# IO.net
KiCad netlist of a schematic drawn in Altium Designer
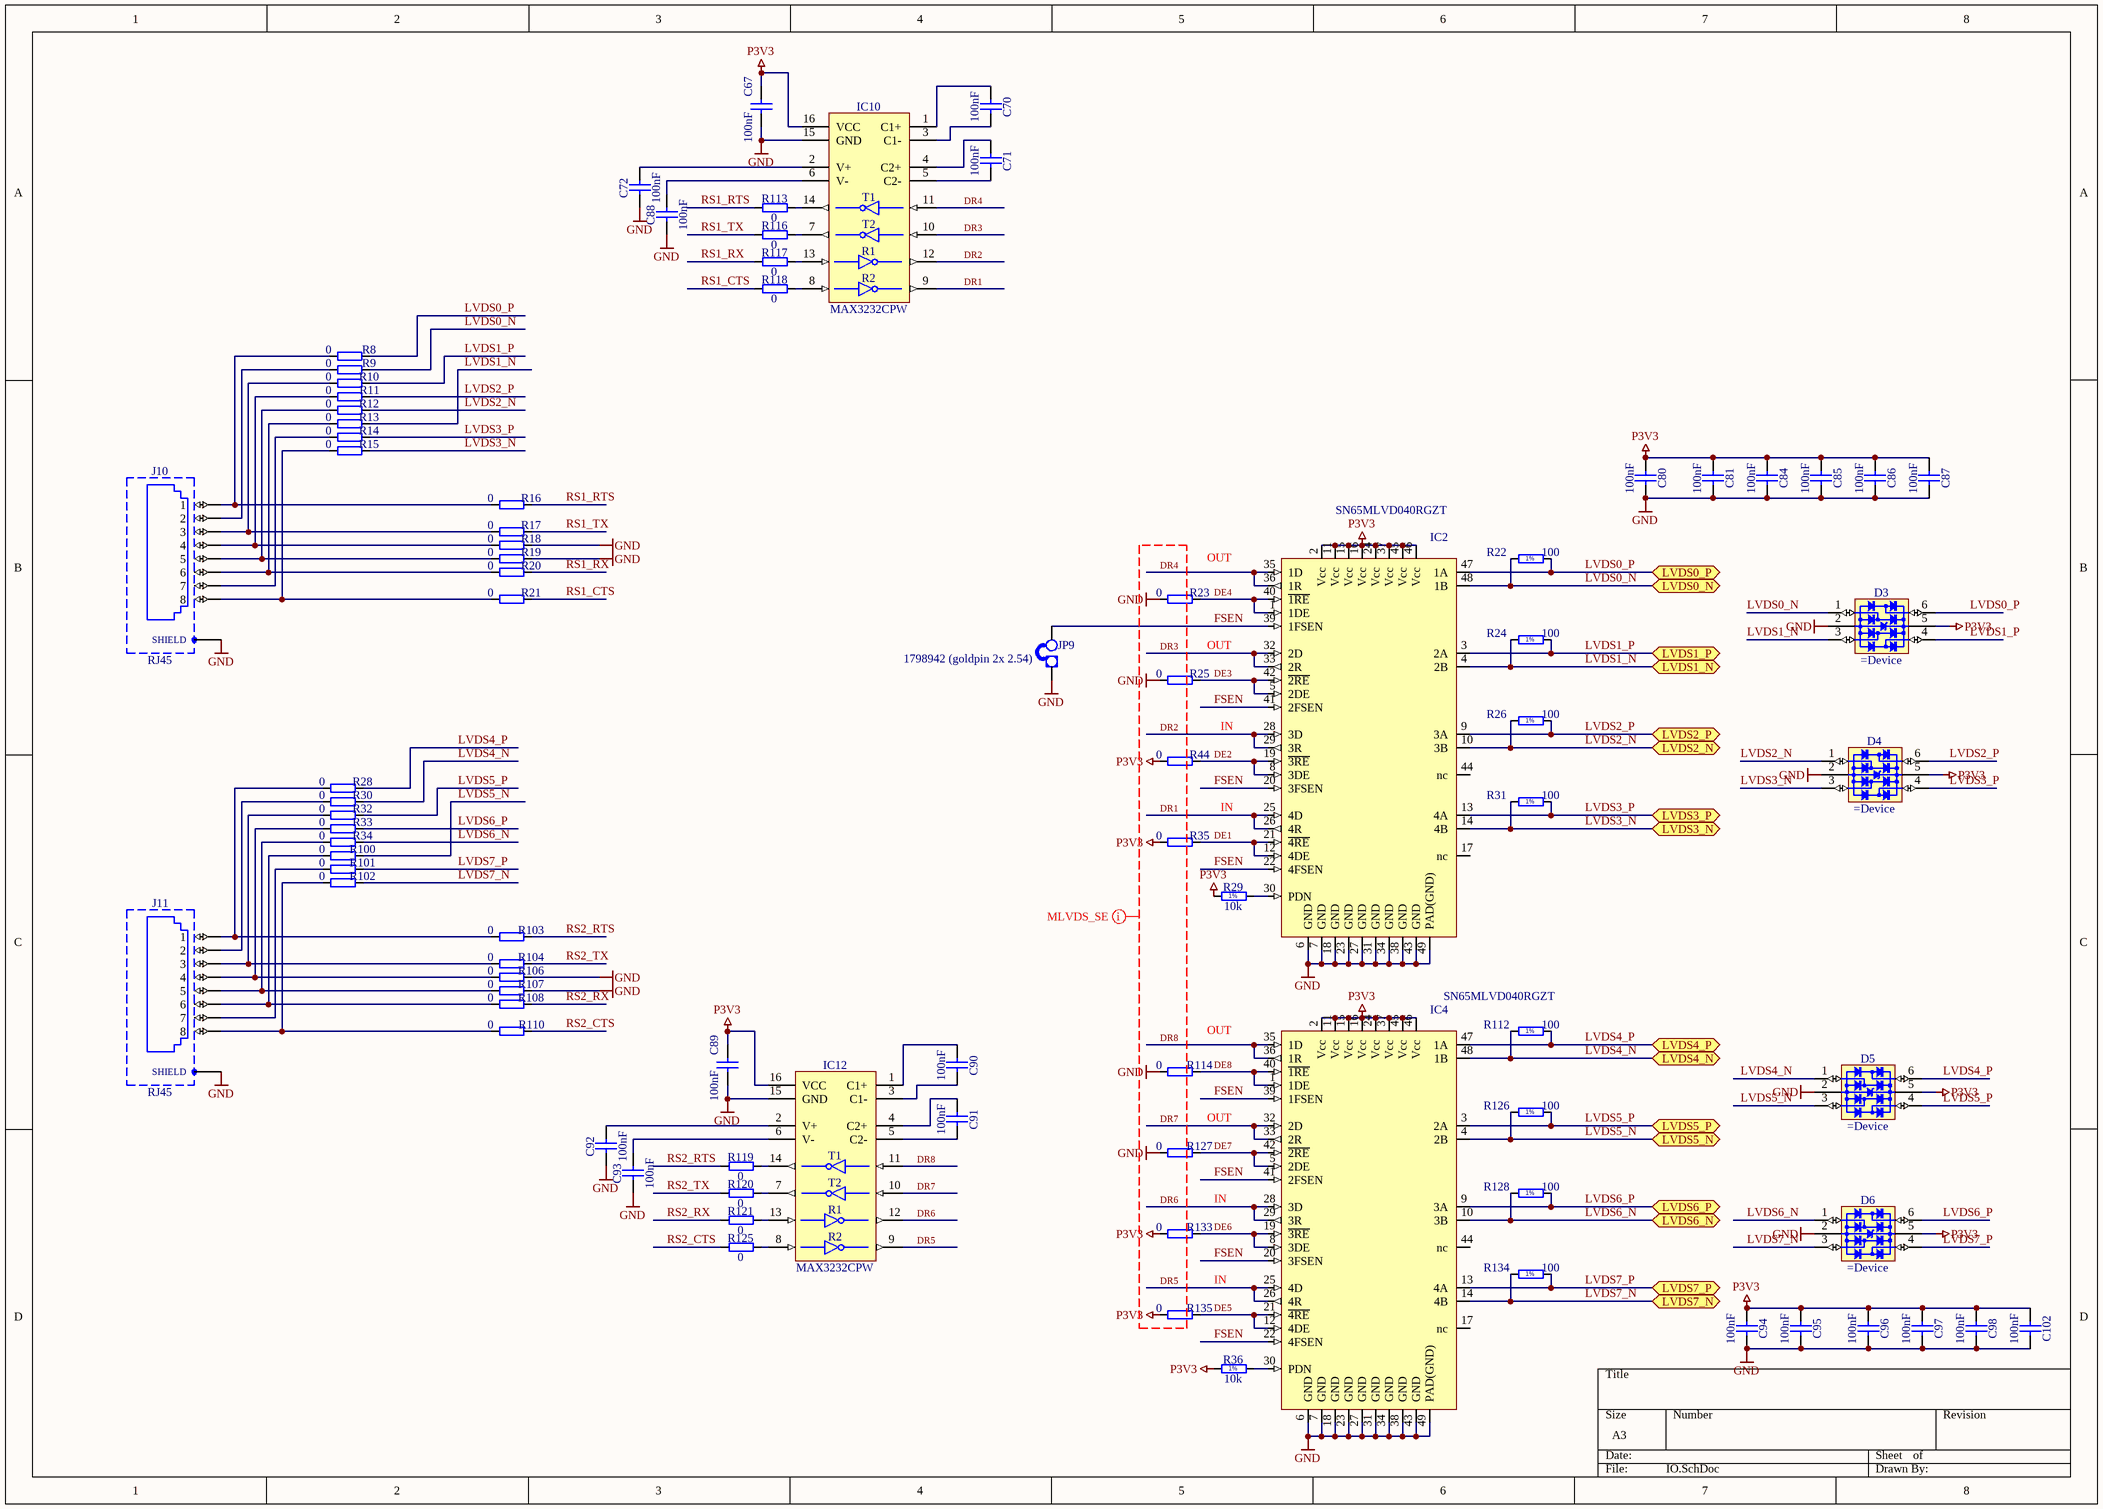
[diagram p0: IO.SchDoc]

(export (version "E")
  (design (tool "Eeschema 10.0.6"))
  (components
    (comp (ref "C67")
      (value "100nF")
      (footprint "CAPC0603X33N")
      (description "Non-polarised capacitor")
      (fields (field (name "PART NUMBER") "CC0201_100NF_6.3V_10%_X5R") (field (name "VOLTAGE") "6.3V"))
      (libsource (lib "Capacitors") (part "Capacitor - non polarized"))
    )
    (comp (ref "C70")
      (value "100nF")
      (footprint "CAPC1608X90N")
      (description "Non-polarised capacitor")
      (fields (field (name "PART NUMBER") "CC0603_100NF_100V_10%_X7R") (field (name "VOLTAGE") "100V"))
      (libsource (lib "Capacitors") (part "Capacitor - non polarized"))
    )
    (comp (ref "C71")
      (value "100nF")
      (footprint "CAPC1608X90N")
      (description "Non-polarised capacitor")
      (fields (field (name "PART NUMBER") "CC0603_100NF_100V_10%_X7R") (field (name "VOLTAGE") "100V"))
      (libsource (lib "Capacitors") (part "Capacitor - non polarized"))
    )
    (comp (ref "C72")
      (value "100nF")
      (footprint "CAPC1608X90N")
      (description "Non-polarised capacitor")
      (fields (field (name "PART NUMBER") "CC0603_100NF_100V_10%_X7R") (field (name "VOLTAGE") "100V"))
      (libsource (lib "Capacitors") (part "Capacitor - non polarized"))
    )
    (comp (ref "C80")
      (value "100nF")
      (footprint "CAPC0603X33N")
      (description "Non-polarised capacitor")
      (fields (field (name "PART NUMBER") "CC0201_100NF_6.3V_10%_X5R") (field (name "VOLTAGE") "6.3V"))
      (libsource (lib "Capacitors") (part "Capacitor - non polarized"))
    )
    (comp (ref "C81")
      (value "100nF")
      (footprint "CAPC0603X33N")
      (description "Non-polarised capacitor")
      (fields (field (name "PART NUMBER") "CC0201_100NF_6.3V_10%_X5R") (field (name "VOLTAGE") "6.3V"))
      (libsource (lib "Capacitors") (part "Capacitor - non polarized"))
    )
    (comp (ref "C84")
      (value "100nF")
      (footprint "CAPC0603X33N")
      (description "Non-polarised capacitor")
      (fields (field (name "PART NUMBER") "CC0201_100NF_6.3V_10%_X5R") (field (name "VOLTAGE") "6.3V"))
      (libsource (lib "Capacitors") (part "Capacitor - non polarized"))
    )
    (comp (ref "C85")
      (value "100nF")
      (footprint "CAPC0603X33N")
      (description "Non-polarised capacitor")
      (fields (field (name "PART NUMBER") "CC0201_100NF_6.3V_10%_X5R") (field (name "VOLTAGE") "6.3V"))
      (libsource (lib "Capacitors") (part "Capacitor - non polarized"))
    )
    (comp (ref "C86")
      (value "100nF")
      (footprint "CAPC0603X33N")
      (description "Non-polarised capacitor")
      (fields (field (name "PART NUMBER") "CC0201_100NF_6.3V_10%_X5R") (field (name "VOLTAGE") "6.3V"))
      (libsource (lib "Capacitors") (part "Capacitor - non polarized"))
    )
    (comp (ref "C87")
      (value "100nF")
      (footprint "CAPC0603X33N")
      (description "Non-polarised capacitor")
      (fields (field (name "PART NUMBER") "CC0201_100NF_6.3V_10%_X5R") (field (name "VOLTAGE") "6.3V"))
      (libsource (lib "Capacitors") (part "Capacitor - non polarized"))
    )
    (comp (ref "C88")
      (value "100nF")
      (footprint "CAPC1608X90N")
      (description "Non-polarised capacitor")
      (fields (field (name "PART NUMBER") "CC0603_100NF_100V_10%_X7R") (field (name "VOLTAGE") "100V"))
      (libsource (lib "Capacitors") (part "Capacitor - non polarized"))
    )
    (comp (ref "C89")
      (value "100nF")
      (footprint "CAPC0603X33N")
      (description "Non-polarised capacitor")
      (fields (field (name "PART NUMBER") "CC0201_100NF_6.3V_10%_X5R") (field (name "VOLTAGE") "6.3V"))
      (libsource (lib "Capacitors") (part "Capacitor - non polarized"))
    )
    (comp (ref "C90")
      (value "100nF")
      (footprint "CAPC1608X90N")
      (description "Non-polarised capacitor")
      (fields (field (name "PART NUMBER") "CC0603_100NF_100V_10%_X7R") (field (name "VOLTAGE") "100V"))
      (libsource (lib "Capacitors") (part "Capacitor - non polarized"))
    )
    (comp (ref "C91")
      (value "100nF")
      (footprint "CAPC1608X90N")
      (description "Non-polarised capacitor")
      (fields (field (name "PART NUMBER") "CC0603_100NF_100V_10%_X7R") (field (name "VOLTAGE") "100V"))
      (libsource (lib "Capacitors") (part "Capacitor - non polarized"))
    )
    (comp (ref "C92")
      (value "100nF")
      (footprint "CAPC1608X90N")
      (description "Non-polarised capacitor")
      (fields (field (name "PART NUMBER") "CC0603_100NF_100V_10%_X7R") (field (name "VOLTAGE") "100V"))
      (libsource (lib "Capacitors") (part "Capacitor - non polarized"))
    )
    (comp (ref "C93")
      (value "100nF")
      (footprint "CAPC1608X90N")
      (description "Non-polarised capacitor")
      (fields (field (name "PART NUMBER") "CC0603_100NF_100V_10%_X7R") (field (name "VOLTAGE") "100V"))
      (libsource (lib "Capacitors") (part "Capacitor - non polarized"))
    )
    (comp (ref "C94")
      (value "100nF")
      (footprint "CAPC0603X33N")
      (description "Non-polarised capacitor")
      (fields (field (name "PART NUMBER") "CC0201_100NF_6.3V_10%_X5R") (field (name "VOLTAGE") "6.3V"))
      (libsource (lib "Capacitors") (part "Capacitor - non polarized"))
    )
    (comp (ref "C95")
      (value "100nF")
      (footprint "CAPC0603X33N")
      (description "Non-polarised capacitor")
      (fields (field (name "PART NUMBER") "CC0201_100NF_6.3V_10%_X5R") (field (name "VOLTAGE") "6.3V"))
      (libsource (lib "Capacitors") (part "Capacitor - non polarized"))
    )
    (comp (ref "C96")
      (value "100nF")
      (footprint "CAPC0603X33N")
      (description "Non-polarised capacitor")
      (fields (field (name "PART NUMBER") "CC0201_100NF_6.3V_10%_X5R") (field (name "VOLTAGE") "6.3V"))
      (libsource (lib "Capacitors") (part "Capacitor - non polarized"))
    )
    (comp (ref "C97")
      (value "100nF")
      (footprint "CAPC0603X33N")
      (description "Non-polarised capacitor")
      (fields (field (name "PART NUMBER") "CC0201_100NF_6.3V_10%_X5R") (field (name "VOLTAGE") "6.3V"))
      (libsource (lib "Capacitors") (part "Capacitor - non polarized"))
    )
    (comp (ref "C98")
      (value "100nF")
      (footprint "CAPC0603X33N")
      (description "Non-polarised capacitor")
      (fields (field (name "PART NUMBER") "CC0201_100NF_6.3V_10%_X5R") (field (name "VOLTAGE") "6.3V"))
      (libsource (lib "Capacitors") (part "Capacitor - non polarized"))
    )
    (comp (ref "C102")
      (value "100nF")
      (footprint "CAPC0603X33N")
      (description "Non-polarised capacitor")
      (fields (field (name "PART NUMBER") "CC0201_100NF_6.3V_10%_X5R") (field (name "VOLTAGE") "6.3V"))
      (libsource (lib "Capacitors") (part "Capacitor - non polarized"))
    )
    (comp (ref "D3")
      (value "~")
      (footprint "SOTFL50P160X60-6N")
      (fields (field (name "PART NUMBER") "NUP4114UPXV6T1G"))
      (libsource (lib "ICs And Semiconductors") (part "NUP4114"))
    )
    (comp (ref "D4")
      (value "~")
      (footprint "SOTFL50P160X60-6N")
      (fields (field (name "PART NUMBER") "NUP4114UPXV6T1G"))
      (libsource (lib "ICs And Semiconductors") (part "NUP4114"))
    )
    (comp (ref "D5")
      (value "~")
      (footprint "SOTFL50P160X60-6N")
      (fields (field (name "PART NUMBER") "NUP4114UPXV6T1G"))
      (libsource (lib "ICs And Semiconductors") (part "NUP4114"))
    )
    (comp (ref "D6")
      (value "~")
      (footprint "SOTFL50P160X60-6N")
      (fields (field (name "PART NUMBER") "NUP4114UPXV6T1G"))
      (libsource (lib "ICs And Semiconductors") (part "NUP4114"))
    )
    (comp (ref "IC2")
      (value "SN65MLVD040RGZT")
      (footprint "QFN48L")
      (libsource (lib "LIBRARY_SCH") (part "IFC_SN65MLVD040"))
    )
    (comp (ref "IC4")
      (value "SN65MLVD040RGZT")
      (footprint "QFN48L")
      (libsource (lib "LIBRARY_SCH") (part "IFC_SN65MLVD040"))
    )
    (comp (ref "IC10")
      (value "MAX3232CPW")
      (footprint "SOP65P640X120-16N")
      (description "3-V To 5.5-V Multichannel RS-232 Line Driver/Receiver With ±15kV IEC ESD Protection")
      (fields (field (name "MANUFACTURER") "TEXAS INSTRUMENTS"))
      (libsource (lib "ICs And Semiconductors") (part "MAX3232CPW"))
    )
    (comp (ref "IC12")
      (value "MAX3232CPW")
      (footprint "SOP65P640X120-16N")
      (description "3-V To 5.5-V Multichannel RS-232 Line Driver/Receiver With ±15kV IEC ESD Protection")
      (fields (field (name "MANUFACTURER") "TEXAS INSTRUMENTS"))
      (libsource (lib "ICs And Semiconductors") (part "MAX3232CPW"))
    )
    (comp (ref "J10")
      (value "RJ45")
      (footprint "FCI_95678-001LF")
      (description "1 Port, 8 Positions Shielded Snap PEG, CAT5 RJ45 Horizontal Modular Jack")
      (fields (field (name "PART NUMBER") "FCI_95678-001LF") (field (name "MANUFACTURER") "FCI"))
      (libsource (lib "Connectors") (part "FCI_95678-001LF"))
    )
    (comp (ref "J11")
      (value "RJ45")
      (footprint "FCI_95678-001LF")
      (description "1 Port, 8 Positions Shielded Snap PEG, CAT5 RJ45 Horizontal Modular Jack")
      (fields (field (name "PART NUMBER") "FCI_95678-001LF") (field (name "MANUFACTURER") "FCI"))
      (libsource (lib "Connectors") (part "FCI_95678-001LF"))
    )
    (comp (ref "JP9")
      (value "1798942 (goldpin 2x 2.54)")
      (footprint "jump")
      (description "Jumper")
      (libsource (lib "LIBRARY_SCH") (part "JUMPER"))
    )
    (comp (ref "R8")
      (value "0")
      (footprint "RESC1005X40N")
      (description "Resistor")
      (fields (field (name "PART NUMBER") "R0402_0R_JUMPER") (field (name "MANUFACTURER") "GENERIC"))
      (libsource (lib "Resistors") (part "Resistor"))
    )
    (comp (ref "R9")
      (value "0")
      (footprint "RESC1005X40N")
      (description "Resistor")
      (fields (field (name "PART NUMBER") "R0402_0R_JUMPER") (field (name "MANUFACTURER") "GENERIC"))
      (libsource (lib "Resistors") (part "Resistor"))
    )
    (comp (ref "R10")
      (value "0")
      (footprint "RESC1005X40N")
      (description "Resistor")
      (fields (field (name "PART NUMBER") "R0402_0R_JUMPER") (field (name "MANUFACTURER") "GENERIC"))
      (libsource (lib "Resistors") (part "Resistor"))
    )
    (comp (ref "R11")
      (value "0")
      (footprint "RESC1005X40N")
      (description "Resistor")
      (fields (field (name "PART NUMBER") "R0402_0R_JUMPER") (field (name "MANUFACTURER") "GENERIC"))
      (libsource (lib "Resistors") (part "Resistor"))
    )
    (comp (ref "R12")
      (value "0")
      (footprint "RESC1005X40N")
      (description "Resistor")
      (fields (field (name "PART NUMBER") "R0402_0R_JUMPER") (field (name "MANUFACTURER") "GENERIC"))
      (libsource (lib "Resistors") (part "Resistor"))
    )
    (comp (ref "R13")
      (value "0")
      (footprint "RESC1005X40N")
      (description "Resistor")
      (fields (field (name "PART NUMBER") "R0402_0R_JUMPER") (field (name "MANUFACTURER") "GENERIC"))
      (libsource (lib "Resistors") (part "Resistor"))
    )
    (comp (ref "R14")
      (value "0")
      (footprint "RESC1005X40N")
      (description "Resistor")
      (fields (field (name "PART NUMBER") "R0402_0R_JUMPER") (field (name "MANUFACTURER") "GENERIC"))
      (libsource (lib "Resistors") (part "Resistor"))
    )
    (comp (ref "R15")
      (value "0")
      (footprint "RESC1005X40N")
      (description "Resistor")
      (fields (field (name "PART NUMBER") "R0402_0R_JUMPER") (field (name "MANUFACTURER") "GENERIC"))
      (libsource (lib "Resistors") (part "Resistor"))
    )
    (comp (ref "R16")
      (value "0")
      (footprint "RESC1005X40N")
      (description "Resistor")
      (fields (field (name "PART NUMBER") "R0402_0R_JUMPER") (field (name "MANUFACTURER") "GENERIC"))
      (libsource (lib "Resistors") (part "Resistor"))
    )
    (comp (ref "R17")
      (value "0")
      (footprint "RESC1005X40N")
      (description "Resistor")
      (fields (field (name "PART NUMBER") "R0402_0R_JUMPER") (field (name "MANUFACTURER") "GENERIC"))
      (libsource (lib "Resistors") (part "Resistor"))
    )
    (comp (ref "R18")
      (value "0")
      (footprint "RESC1005X40N")
      (description "Resistor")
      (fields (field (name "PART NUMBER") "R0402_0R_JUMPER") (field (name "MANUFACTURER") "GENERIC"))
      (libsource (lib "Resistors") (part "Resistor"))
    )
    (comp (ref "R19")
      (value "0")
      (footprint "RESC1005X40N")
      (description "Resistor")
      (fields (field (name "PART NUMBER") "R0402_0R_JUMPER") (field (name "MANUFACTURER") "GENERIC"))
      (libsource (lib "Resistors") (part "Resistor"))
    )
    (comp (ref "R20")
      (value "0")
      (footprint "RESC1005X40N")
      (description "Resistor")
      (fields (field (name "PART NUMBER") "R0402_0R_JUMPER") (field (name "MANUFACTURER") "GENERIC"))
      (libsource (lib "Resistors") (part "Resistor"))
    )
    (comp (ref "R21")
      (value "0")
      (footprint "RESC1005X40N")
      (description "Resistor")
      (fields (field (name "PART NUMBER") "R0402_0R_JUMPER") (field (name "MANUFACTURER") "GENERIC"))
      (libsource (lib "Resistors") (part "Resistor"))
    )
    (comp (ref "R22")
      (value "100")
      (footprint "RESC1005X40N")
      (description "Resistor - 1%")
      (fields (field (name "PART NUMBER") "R0402_100R_1%_0.0625W_100PPM") (field (name "POWER") "0.0625W"))
      (libsource (lib "Resistors") (part "Resistor - 1%"))
    )
    (comp (ref "R23")
      (value "0")
      (footprint "RESC1005X40N")
      (description "Resistor")
      (fields (field (name "PART NUMBER") "R0402_0R_JUMPER") (field (name "MANUFACTURER") "GENERIC"))
      (libsource (lib "Resistors") (part "Resistor"))
    )
    (comp (ref "R24")
      (value "100")
      (footprint "RESC1005X40N")
      (description "Resistor - 1%")
      (fields (field (name "PART NUMBER") "R0402_100R_1%_0.0625W_100PPM") (field (name "POWER") "0.0625W"))
      (libsource (lib "Resistors") (part "Resistor - 1%"))
    )
    (comp (ref "R25")
      (value "0")
      (footprint "RESC1005X40N")
      (description "Resistor")
      (fields (field (name "PART NUMBER") "R0402_0R_JUMPER") (field (name "MANUFACTURER") "GENERIC"))
      (libsource (lib "Resistors") (part "Resistor"))
    )
    (comp (ref "R26")
      (value "100")
      (footprint "RESC1005X40N")
      (description "Resistor - 1%")
      (fields (field (name "PART NUMBER") "R0402_100R_1%_0.0625W_100PPM") (field (name "POWER") "0.0625W"))
      (libsource (lib "Resistors") (part "Resistor - 1%"))
    )
    (comp (ref "R28")
      (value "0")
      (footprint "RESC1005X40N")
      (description "Resistor")
      (fields (field (name "PART NUMBER") "R0402_0R_JUMPER") (field (name "MANUFACTURER") "GENERIC"))
      (libsource (lib "Resistors") (part "Resistor"))
    )
    (comp (ref "R29")
      (value "10k")
      (footprint "RESC1005X40N")
      (description "Resistor - 1%")
      (fields (field (name "PART NUMBER") "R0402_10K_1%_0.0625W_100PPM") (field (name "POWER") "0.0625W"))
      (libsource (lib "Resistors") (part "Resistor - 1%"))
    )
    (comp (ref "R30")
      (value "0")
      (footprint "RESC1005X40N")
      (description "Resistor")
      (fields (field (name "PART NUMBER") "R0402_0R_JUMPER") (field (name "MANUFACTURER") "GENERIC"))
      (libsource (lib "Resistors") (part "Resistor"))
    )
    (comp (ref "R31")
      (value "100")
      (footprint "RESC1005X40N")
      (description "Resistor - 1%")
      (fields (field (name "PART NUMBER") "R0402_100R_1%_0.0625W_100PPM") (field (name "POWER") "0.0625W"))
      (libsource (lib "Resistors") (part "Resistor - 1%"))
    )
    (comp (ref "R32")
      (value "0")
      (footprint "RESC1005X40N")
      (description "Resistor")
      (fields (field (name "PART NUMBER") "R0402_0R_JUMPER") (field (name "MANUFACTURER") "GENERIC"))
      (libsource (lib "Resistors") (part "Resistor"))
    )
    (comp (ref "R33")
      (value "0")
      (footprint "RESC1005X40N")
      (description "Resistor")
      (fields (field (name "PART NUMBER") "R0402_0R_JUMPER") (field (name "MANUFACTURER") "GENERIC"))
      (libsource (lib "Resistors") (part "Resistor"))
    )
    (comp (ref "R34")
      (value "0")
      (footprint "RESC1005X40N")
      (description "Resistor")
      (fields (field (name "PART NUMBER") "R0402_0R_JUMPER") (field (name "MANUFACTURER") "GENERIC"))
      (libsource (lib "Resistors") (part "Resistor"))
    )
    (comp (ref "R35")
      (value "0")
      (footprint "RESC1005X40N")
      (description "Resistor")
      (fields (field (name "PART NUMBER") "R0402_0R_JUMPER") (field (name "MANUFACTURER") "GENERIC"))
      (libsource (lib "Resistors") (part "Resistor"))
    )
    (comp (ref "R36")
      (value "10k")
      (footprint "RESC1005X40N")
      (description "Resistor - 1%")
      (fields (field (name "PART NUMBER") "R0402_10K_1%_0.0625W_100PPM") (field (name "POWER") "0.0625W"))
      (libsource (lib "Resistors") (part "Resistor - 1%"))
    )
    (comp (ref "R44")
      (value "0")
      (footprint "RESC1005X40N")
      (description "Resistor")
      (fields (field (name "PART NUMBER") "R0402_0R_JUMPER") (field (name "MANUFACTURER") "GENERIC"))
      (libsource (lib "Resistors") (part "Resistor"))
    )
    (comp (ref "R100")
      (value "0")
      (footprint "RESC1005X40N")
      (description "Resistor")
      (fields (field (name "PART NUMBER") "R0402_0R_JUMPER") (field (name "MANUFACTURER") "GENERIC"))
      (libsource (lib "Resistors") (part "Resistor"))
    )
    (comp (ref "R101")
      (value "0")
      (footprint "RESC1005X40N")
      (description "Resistor")
      (fields (field (name "PART NUMBER") "R0402_0R_JUMPER") (field (name "MANUFACTURER") "GENERIC"))
      (libsource (lib "Resistors") (part "Resistor"))
    )
    (comp (ref "R102")
      (value "0")
      (footprint "RESC1005X40N")
      (description "Resistor")
      (fields (field (name "PART NUMBER") "R0402_0R_JUMPER") (field (name "MANUFACTURER") "GENERIC"))
      (libsource (lib "Resistors") (part "Resistor"))
    )
    (comp (ref "R103")
      (value "0")
      (footprint "RESC1005X40N")
      (description "Resistor")
      (fields (field (name "PART NUMBER") "R0402_0R_JUMPER") (field (name "MANUFACTURER") "GENERIC"))
      (libsource (lib "Resistors") (part "Resistor"))
    )
    (comp (ref "R104")
      (value "0")
      (footprint "RESC1005X40N")
      (description "Resistor")
      (fields (field (name "PART NUMBER") "R0402_0R_JUMPER") (field (name "MANUFACTURER") "GENERIC"))
      (libsource (lib "Resistors") (part "Resistor"))
    )
    (comp (ref "R106")
      (value "0")
      (footprint "RESC1005X40N")
      (description "Resistor")
      (fields (field (name "PART NUMBER") "R0402_0R_JUMPER") (field (name "MANUFACTURER") "GENERIC"))
      (libsource (lib "Resistors") (part "Resistor"))
    )
    (comp (ref "R107")
      (value "0")
      (footprint "RESC1005X40N")
      (description "Resistor")
      (fields (field (name "PART NUMBER") "R0402_0R_JUMPER") (field (name "MANUFACTURER") "GENERIC"))
      (libsource (lib "Resistors") (part "Resistor"))
    )
    (comp (ref "R108")
      (value "0")
      (footprint "RESC1005X40N")
      (description "Resistor")
      (fields (field (name "PART NUMBER") "R0402_0R_JUMPER") (field (name "MANUFACTURER") "GENERIC"))
      (libsource (lib "Resistors") (part "Resistor"))
    )
    (comp (ref "R110")
      (value "0")
      (footprint "RESC1005X40N")
      (description "Resistor")
      (fields (field (name "PART NUMBER") "R0402_0R_JUMPER") (field (name "MANUFACTURER") "GENERIC"))
      (libsource (lib "Resistors") (part "Resistor"))
    )
    (comp (ref "R112")
      (value "100")
      (footprint "RESC1005X40N")
      (description "Resistor - 1%")
      (fields (field (name "PART NUMBER") "R0402_100R_1%_0.0625W_100PPM") (field (name "POWER") "0.0625W"))
      (libsource (lib "Resistors") (part "Resistor - 1%"))
    )
    (comp (ref "R113")
      (value "0")
      (footprint "RESC1005X40N")
      (description "Resistor")
      (fields (field (name "PART NUMBER") "R0402_0R_JUMPER") (field (name "MANUFACTURER") "GENERIC"))
      (libsource (lib "Resistors") (part "Resistor"))
    )
    (comp (ref "R114")
      (value "0")
      (footprint "RESC1005X40N")
      (description "Resistor")
      (fields (field (name "PART NUMBER") "R0402_0R_JUMPER") (field (name "MANUFACTURER") "GENERIC"))
      (libsource (lib "Resistors") (part "Resistor"))
    )
    (comp (ref "R116")
      (value "0")
      (footprint "RESC1005X40N")
      (description "Resistor")
      (fields (field (name "PART NUMBER") "R0402_0R_JUMPER") (field (name "MANUFACTURER") "GENERIC"))
      (libsource (lib "Resistors") (part "Resistor"))
    )
    (comp (ref "R117")
      (value "0")
      (footprint "RESC1005X40N")
      (description "Resistor")
      (fields (field (name "PART NUMBER") "R0402_0R_JUMPER") (field (name "MANUFACTURER") "GENERIC"))
      (libsource (lib "Resistors") (part "Resistor"))
    )
    (comp (ref "R118")
      (value "0")
      (footprint "RESC1005X40N")
      (description "Resistor")
      (fields (field (name "PART NUMBER") "R0402_0R_JUMPER") (field (name "MANUFACTURER") "GENERIC"))
      (libsource (lib "Resistors") (part "Resistor"))
    )
    (comp (ref "R119")
      (value "0")
      (footprint "RESC1005X40N")
      (description "Resistor")
      (fields (field (name "PART NUMBER") "R0402_0R_JUMPER") (field (name "MANUFACTURER") "GENERIC"))
      (libsource (lib "Resistors") (part "Resistor"))
    )
    (comp (ref "R120")
      (value "0")
      (footprint "RESC1005X40N")
      (description "Resistor")
      (fields (field (name "PART NUMBER") "R0402_0R_JUMPER") (field (name "MANUFACTURER") "GENERIC"))
      (libsource (lib "Resistors") (part "Resistor"))
    )
    (comp (ref "R121")
      (value "0")
      (footprint "RESC1005X40N")
      (description "Resistor")
      (fields (field (name "PART NUMBER") "R0402_0R_JUMPER") (field (name "MANUFACTURER") "GENERIC"))
      (libsource (lib "Resistors") (part "Resistor"))
    )
    (comp (ref "R125")
      (value "0")
      (footprint "RESC1005X40N")
      (description "Resistor")
      (fields (field (name "PART NUMBER") "R0402_0R_JUMPER") (field (name "MANUFACTURER") "GENERIC"))
      (libsource (lib "Resistors") (part "Resistor"))
    )
    (comp (ref "R126")
      (value "100")
      (footprint "RESC1005X40N")
      (description "Resistor - 1%")
      (fields (field (name "PART NUMBER") "R0402_100R_1%_0.0625W_100PPM") (field (name "POWER") "0.0625W"))
      (libsource (lib "Resistors") (part "Resistor - 1%"))
    )
    (comp (ref "R127")
      (value "0")
      (footprint "RESC1005X40N")
      (description "Resistor")
      (fields (field (name "PART NUMBER") "R0402_0R_JUMPER") (field (name "MANUFACTURER") "GENERIC"))
      (libsource (lib "Resistors") (part "Resistor"))
    )
    (comp (ref "R128")
      (value "100")
      (footprint "RESC1005X40N")
      (description "Resistor - 1%")
      (fields (field (name "PART NUMBER") "R0402_100R_1%_0.0625W_100PPM") (field (name "POWER") "0.0625W"))
      (libsource (lib "Resistors") (part "Resistor - 1%"))
    )
    (comp (ref "R133")
      (value "0")
      (footprint "RESC1005X40N")
      (description "Resistor")
      (fields (field (name "PART NUMBER") "R0402_0R_JUMPER") (field (name "MANUFACTURER") "GENERIC"))
      (libsource (lib "Resistors") (part "Resistor"))
    )
    (comp (ref "R134")
      (value "100")
      (footprint "RESC1005X40N")
      (description "Resistor - 1%")
      (fields (field (name "PART NUMBER") "R0402_100R_1%_0.0625W_100PPM") (field (name "POWER") "0.0625W"))
      (libsource (lib "Resistors") (part "Resistor - 1%"))
    )
    (comp (ref "R135")
      (value "0")
      (footprint "RESC1005X40N")
      (description "Resistor")
      (fields (field (name "PART NUMBER") "R0402_0R_JUMPER") (field (name "MANUFACTURER") "GENERIC"))
      (libsource (lib "Resistors") (part "Resistor"))
    )
  )
  (nets
    (net (code "1") (name "/DE1") (class "Default")
      (node (ref "IC2") (pin "12") (pinfunction "4DE_12") (pintype "input"))
      (node (ref "IC2") (pin "21") (pinfunction "~{4RE}_21") (pintype "input"))
      (node (ref "R35") (pin "2") (pinfunction "2_2") (pintype "passive"))
    )
    (net (code "2") (name "/DE2") (class "Default")
      (node (ref "IC2") (pin "19") (pinfunction "~{3RE}_19") (pintype "input"))
      (node (ref "IC2") (pin "8") (pinfunction "3DE_8") (pintype "input"))
      (node (ref "R44") (pin "2") (pinfunction "2_2") (pintype "passive"))
    )
    (net (code "3") (name "/DE3") (class "Default")
      (node (ref "IC2") (pin "42") (pinfunction "~{2RE}_42") (pintype "input"))
      (node (ref "IC2") (pin "5") (pinfunction "2DE_5") (pintype "input"))
      (node (ref "R25") (pin "2") (pinfunction "2_2") (pintype "passive"))
    )
    (net (code "4") (name "/DE4") (class "Default")
      (node (ref "IC2") (pin "1") (pinfunction "1DE_1") (pintype "input"))
      (node (ref "IC2") (pin "40") (pinfunction "~{1RE}_40") (pintype "input"))
      (node (ref "R23") (pin "2") (pinfunction "2_2") (pintype "passive"))
    )
    (net (code "5") (name "/DE5") (class "Default")
      (node (ref "IC4") (pin "12") (pinfunction "4DE_12") (pintype "input"))
      (node (ref "IC4") (pin "21") (pinfunction "~{4RE}_21") (pintype "input"))
      (node (ref "R135") (pin "2") (pinfunction "2_2") (pintype "passive"))
    )
    (net (code "6") (name "/DE6") (class "Default")
      (node (ref "IC4") (pin "19") (pinfunction "~{3RE}_19") (pintype "input"))
      (node (ref "IC4") (pin "8") (pinfunction "3DE_8") (pintype "input"))
      (node (ref "R133") (pin "2") (pinfunction "2_2") (pintype "passive"))
    )
    (net (code "7") (name "/DE7") (class "Default")
      (node (ref "IC4") (pin "42") (pinfunction "~{2RE}_42") (pintype "input"))
      (node (ref "IC4") (pin "5") (pinfunction "2DE_5") (pintype "input"))
      (node (ref "R127") (pin "2") (pinfunction "2_2") (pintype "passive"))
    )
    (net (code "8") (name "/DE8") (class "Default")
      (node (ref "IC4") (pin "1") (pinfunction "1DE_1") (pintype "input"))
      (node (ref "IC4") (pin "40") (pinfunction "~{1RE}_40") (pintype "input"))
      (node (ref "R114") (pin "2") (pinfunction "2_2") (pintype "passive"))
    )
    (net (code "9") (name "/DR1") (class "Default")
      (node (ref "IC10") (pin "9") (pinfunction "R2OUT_9") (pintype "output"))
      (node (ref "IC2") (pin "25") (pinfunction "4D_25") (pintype "input"))
      (node (ref "IC2") (pin "26") (pinfunction "4R_26") (pintype "output"))
    )
    (net (code "10") (name "/DR2") (class "Default")
      (node (ref "IC10") (pin "12") (pinfunction "R1OUT_12") (pintype "output"))
      (node (ref "IC2") (pin "28") (pinfunction "3D_28") (pintype "input"))
      (node (ref "IC2") (pin "29") (pinfunction "3R_29") (pintype "output"))
    )
    (net (code "11") (name "/DR3") (class "Default")
      (node (ref "IC10") (pin "10") (pinfunction "T2IN_10") (pintype "input"))
      (node (ref "IC2") (pin "32") (pinfunction "2D_32") (pintype "input"))
      (node (ref "IC2") (pin "33") (pinfunction "2R_33") (pintype "output"))
    )
    (net (code "12") (name "/DR4") (class "Default")
      (node (ref "IC10") (pin "11") (pinfunction "T1IN_11") (pintype "input"))
      (node (ref "IC2") (pin "35") (pinfunction "1D_35") (pintype "input"))
      (node (ref "IC2") (pin "36") (pinfunction "1R_36") (pintype "output"))
    )
    (net (code "13") (name "/DR5") (class "Default")
      (node (ref "IC12") (pin "9") (pinfunction "R2OUT_9") (pintype "output"))
      (node (ref "IC4") (pin "25") (pinfunction "4D_25") (pintype "input"))
      (node (ref "IC4") (pin "26") (pinfunction "4R_26") (pintype "output"))
    )
    (net (code "14") (name "/DR6") (class "Default")
      (node (ref "IC12") (pin "12") (pinfunction "R1OUT_12") (pintype "output"))
      (node (ref "IC4") (pin "28") (pinfunction "3D_28") (pintype "input"))
      (node (ref "IC4") (pin "29") (pinfunction "3R_29") (pintype "output"))
    )
    (net (code "15") (name "/DR7") (class "Default")
      (node (ref "IC12") (pin "10") (pinfunction "T2IN_10") (pintype "input"))
      (node (ref "IC4") (pin "32") (pinfunction "2D_32") (pintype "input"))
      (node (ref "IC4") (pin "33") (pinfunction "2R_33") (pintype "output"))
    )
    (net (code "16") (name "/DR8") (class "Default")
      (node (ref "IC12") (pin "11") (pinfunction "T1IN_11") (pintype "input"))
      (node (ref "IC4") (pin "35") (pinfunction "1D_35") (pintype "input"))
      (node (ref "IC4") (pin "36") (pinfunction "1R_36") (pintype "output"))
    )
    (net (code "17") (name "/FSEN") (class "Default")
      (node (ref "IC2") (pin "20") (pinfunction "3FSEN_20") (pintype "input"))
      (node (ref "IC2") (pin "22") (pinfunction "4FSEN_22") (pintype "input"))
      (node (ref "IC2") (pin "39") (pinfunction "1FSEN_39") (pintype "input"))
      (node (ref "IC2") (pin "41") (pinfunction "2FSEN_41") (pintype "input"))
      (node (ref "IC4") (pin "20") (pinfunction "3FSEN_20") (pintype "input"))
      (node (ref "IC4") (pin "22") (pinfunction "4FSEN_22") (pintype "input"))
      (node (ref "IC4") (pin "39") (pinfunction "1FSEN_39") (pintype "input"))
      (node (ref "IC4") (pin "41") (pinfunction "2FSEN_41") (pintype "input"))
      (node (ref "JP9") (pin "2") (pinfunction "E2_2") (pintype "passive"))
    )
    (net (code "18") (name "/LVDS0_N") (class "Default")
      (node (ref "D3") (pin "1") (pinfunction "I/O1_1") (pintype "bidirectional"))
      (node (ref "IC2") (pin "48") (pinfunction "1B_48") (pintype "bidirectional"))
      (node (ref "R22") (pin "1") (pinfunction "1_1") (pintype "passive"))
      (node (ref "R9") (pin "2") (pinfunction "2_2") (pintype "passive"))
    )
    (net (code "19") (name "/LVDS0_P") (class "Default")
      (node (ref "D3") (pin "6") (pinfunction "I/O4_6") (pintype "bidirectional"))
      (node (ref "IC2") (pin "47") (pinfunction "1A_47") (pintype "bidirectional"))
      (node (ref "R22") (pin "2") (pinfunction "2_2") (pintype "passive"))
      (node (ref "R8") (pin "2") (pinfunction "2_2") (pintype "passive"))
    )
    (net (code "20") (name "/LVDS1_N") (class "Default")
      (node (ref "D3") (pin "3") (pinfunction "I/O2_3") (pintype "bidirectional"))
      (node (ref "IC2") (pin "4") (pinfunction "2B_4") (pintype "bidirectional"))
      (node (ref "R13") (pin "2") (pinfunction "2_2") (pintype "passive"))
      (node (ref "R24") (pin "1") (pinfunction "1_1") (pintype "passive"))
    )
    (net (code "21") (name "/LVDS1_P") (class "Default")
      (node (ref "D3") (pin "4") (pinfunction "I/O3_4") (pintype "bidirectional"))
      (node (ref "IC2") (pin "3") (pinfunction "2A_3") (pintype "bidirectional"))
      (node (ref "R10") (pin "2") (pinfunction "2_2") (pintype "passive"))
      (node (ref "R24") (pin "2") (pinfunction "2_2") (pintype "passive"))
    )
    (net (code "22") (name "/LVDS2_N") (class "Default")
      (node (ref "D4") (pin "1") (pinfunction "I/O1_1") (pintype "bidirectional"))
      (node (ref "IC2") (pin "10") (pinfunction "3B_10") (pintype "bidirectional"))
      (node (ref "R12") (pin "2") (pinfunction "2_2") (pintype "passive"))
      (node (ref "R26") (pin "1") (pinfunction "1_1") (pintype "passive"))
    )
    (net (code "23") (name "/LVDS2_P") (class "Default")
      (node (ref "D4") (pin "6") (pinfunction "I/O4_6") (pintype "bidirectional"))
      (node (ref "IC2") (pin "9") (pinfunction "3A_9") (pintype "bidirectional"))
      (node (ref "R11") (pin "2") (pinfunction "2_2") (pintype "passive"))
      (node (ref "R26") (pin "2") (pinfunction "2_2") (pintype "passive"))
    )
    (net (code "24") (name "/LVDS3_N") (class "Default")
      (node (ref "D4") (pin "3") (pinfunction "I/O2_3") (pintype "bidirectional"))
      (node (ref "IC2") (pin "14") (pinfunction "4B_14") (pintype "bidirectional"))
      (node (ref "R15") (pin "2") (pinfunction "2_2") (pintype "passive"))
      (node (ref "R31") (pin "1") (pinfunction "1_1") (pintype "passive"))
    )
    (net (code "25") (name "/LVDS3_P") (class "Default")
      (node (ref "D4") (pin "4") (pinfunction "I/O3_4") (pintype "bidirectional"))
      (node (ref "IC2") (pin "13") (pinfunction "4A_13") (pintype "bidirectional"))
      (node (ref "R14") (pin "2") (pinfunction "2_2") (pintype "passive"))
      (node (ref "R31") (pin "2") (pinfunction "2_2") (pintype "passive"))
    )
    (net (code "26") (name "/LVDS4_N") (class "Default")
      (node (ref "D5") (pin "1") (pinfunction "I/O1_1") (pintype "bidirectional"))
      (node (ref "IC4") (pin "48") (pinfunction "1B_48") (pintype "bidirectional"))
      (node (ref "R112") (pin "1") (pinfunction "1_1") (pintype "passive"))
      (node (ref "R30") (pin "2") (pinfunction "2_2") (pintype "passive"))
    )
    (net (code "27") (name "/LVDS4_P") (class "Default")
      (node (ref "D5") (pin "6") (pinfunction "I/O4_6") (pintype "bidirectional"))
      (node (ref "IC4") (pin "47") (pinfunction "1A_47") (pintype "bidirectional"))
      (node (ref "R112") (pin "2") (pinfunction "2_2") (pintype "passive"))
      (node (ref "R28") (pin "2") (pinfunction "2_2") (pintype "passive"))
    )
    (net (code "28") (name "/LVDS5_N") (class "Default")
      (node (ref "D5") (pin "3") (pinfunction "I/O2_3") (pintype "bidirectional"))
      (node (ref "IC4") (pin "4") (pinfunction "2B_4") (pintype "bidirectional"))
      (node (ref "R100") (pin "2") (pinfunction "2_2") (pintype "passive"))
      (node (ref "R126") (pin "1") (pinfunction "1_1") (pintype "passive"))
    )
    (net (code "29") (name "/LVDS5_P") (class "Default")
      (node (ref "D5") (pin "4") (pinfunction "I/O3_4") (pintype "bidirectional"))
      (node (ref "IC4") (pin "3") (pinfunction "2A_3") (pintype "bidirectional"))
      (node (ref "R126") (pin "2") (pinfunction "2_2") (pintype "passive"))
      (node (ref "R32") (pin "2") (pinfunction "2_2") (pintype "passive"))
    )
    (net (code "30") (name "/LVDS6_N") (class "Default")
      (node (ref "D6") (pin "1") (pinfunction "I/O1_1") (pintype "bidirectional"))
      (node (ref "IC4") (pin "10") (pinfunction "3B_10") (pintype "bidirectional"))
      (node (ref "R128") (pin "1") (pinfunction "1_1") (pintype "passive"))
      (node (ref "R34") (pin "2") (pinfunction "2_2") (pintype "passive"))
    )
    (net (code "31") (name "/LVDS6_P") (class "Default")
      (node (ref "D6") (pin "6") (pinfunction "I/O4_6") (pintype "bidirectional"))
      (node (ref "IC4") (pin "9") (pinfunction "3A_9") (pintype "bidirectional"))
      (node (ref "R128") (pin "2") (pinfunction "2_2") (pintype "passive"))
      (node (ref "R33") (pin "2") (pinfunction "2_2") (pintype "passive"))
    )
    (net (code "32") (name "/LVDS7_N") (class "Default")
      (node (ref "D6") (pin "3") (pinfunction "I/O2_3") (pintype "bidirectional"))
      (node (ref "IC4") (pin "14") (pinfunction "4B_14") (pintype "bidirectional"))
      (node (ref "R102") (pin "2") (pinfunction "2_2") (pintype "passive"))
      (node (ref "R134") (pin "1") (pinfunction "1_1") (pintype "passive"))
    )
    (net (code "33") (name "/LVDS7_P") (class "Default")
      (node (ref "D6") (pin "4") (pinfunction "I/O3_4") (pintype "bidirectional"))
      (node (ref "IC4") (pin "13") (pinfunction "4A_13") (pintype "bidirectional"))
      (node (ref "R101") (pin "2") (pinfunction "2_2") (pintype "passive"))
      (node (ref "R134") (pin "2") (pinfunction "2_2") (pintype "passive"))
    )
    (net (code "34") (name "/RS1_CTS") (class "Default")
      (node (ref "R118") (pin "1") (pinfunction "1_1") (pintype "passive"))
      (node (ref "R21") (pin "2") (pinfunction "2_2") (pintype "passive"))
    )
    (net (code "35") (name "/RS1_RTS") (class "Default")
      (node (ref "R113") (pin "1") (pinfunction "1_1") (pintype "passive"))
      (node (ref "R16") (pin "2") (pinfunction "2_2") (pintype "passive"))
    )
    (net (code "36") (name "/RS1_RX") (class "Default")
      (node (ref "R117") (pin "1") (pinfunction "1_1") (pintype "passive"))
      (node (ref "R20") (pin "2") (pinfunction "2_2") (pintype "passive"))
    )
    (net (code "37") (name "/RS1_TX") (class "Default")
      (node (ref "R116") (pin "1") (pinfunction "1_1") (pintype "passive"))
      (node (ref "R17") (pin "2") (pinfunction "2_2") (pintype "passive"))
    )
    (net (code "38") (name "/RS2_CTS") (class "Default")
      (node (ref "R110") (pin "2") (pinfunction "2_2") (pintype "passive"))
      (node (ref "R125") (pin "1") (pinfunction "1_1") (pintype "passive"))
    )
    (net (code "39") (name "/RS2_RTS") (class "Default")
      (node (ref "R103") (pin "2") (pinfunction "2_2") (pintype "passive"))
      (node (ref "R119") (pin "1") (pinfunction "1_1") (pintype "passive"))
    )
    (net (code "40") (name "/RS2_RX") (class "Default")
      (node (ref "R108") (pin "2") (pinfunction "2_2") (pintype "passive"))
      (node (ref "R121") (pin "1") (pinfunction "1_1") (pintype "passive"))
    )
    (net (code "41") (name "/RS2_TX") (class "Default")
      (node (ref "R104") (pin "2") (pinfunction "2_2") (pintype "passive"))
      (node (ref "R120") (pin "1") (pinfunction "1_1") (pintype "passive"))
    )
    (net (code "42") (name "GND") (class "Default")
      (node (ref "C102") (pin "2") (pinfunction "2_2") (pintype "passive"))
      (node (ref "C67") (pin "1") (pinfunction "1_1") (pintype "passive"))
      (node (ref "C72") (pin "2") (pinfunction "2_2") (pintype "passive"))
      (node (ref "C80") (pin "2") (pinfunction "2_2") (pintype "passive"))
      (node (ref "C81") (pin "2") (pinfunction "2_2") (pintype "passive"))
      (node (ref "C84") (pin "2") (pinfunction "2_2") (pintype "passive"))
      (node (ref "C85") (pin "2") (pinfunction "2_2") (pintype "passive"))
      (node (ref "C86") (pin "2") (pinfunction "2_2") (pintype "passive"))
      (node (ref "C87") (pin "2") (pinfunction "2_2") (pintype "passive"))
      (node (ref "C88") (pin "2") (pinfunction "2_2") (pintype "passive"))
      (node (ref "C89") (pin "1") (pinfunction "1_1") (pintype "passive"))
      (node (ref "C92") (pin "2") (pinfunction "2_2") (pintype "passive"))
      (node (ref "C93") (pin "2") (pinfunction "2_2") (pintype "passive"))
      (node (ref "C94") (pin "2") (pinfunction "2_2") (pintype "passive"))
      (node (ref "C95") (pin "2") (pinfunction "2_2") (pintype "passive"))
      (node (ref "C96") (pin "2") (pinfunction "2_2") (pintype "passive"))
      (node (ref "C97") (pin "2") (pinfunction "2_2") (pintype "passive"))
      (node (ref "C98") (pin "2") (pinfunction "2_2") (pintype "passive"))
      (node (ref "D3") (pin "2") (pinfunction "GND_2") (pintype "power_in"))
      (node (ref "D4") (pin "2") (pinfunction "GND_2") (pintype "power_in"))
      (node (ref "D5") (pin "2") (pinfunction "GND_2") (pintype "power_in"))
      (node (ref "D6") (pin "2") (pinfunction "GND_2") (pintype "power_in"))
      (node (ref "IC10") (pin "15") (pinfunction "GND_15") (pintype "power_in"))
      (node (ref "IC12") (pin "15") (pinfunction "GND_15") (pintype "power_in"))
      (node (ref "IC2") (pin "18") (pinfunction "GND_18") (pintype "power_in"))
      (node (ref "IC2") (pin "23") (pinfunction "GND_23") (pintype "power_in"))
      (node (ref "IC2") (pin "27") (pinfunction "GND_27") (pintype "power_in"))
      (node (ref "IC2") (pin "31") (pinfunction "GND_31") (pintype "power_in"))
      (node (ref "IC2") (pin "34") (pinfunction "GND_34") (pintype "power_in"))
      (node (ref "IC2") (pin "38") (pinfunction "GND_38") (pintype "power_in"))
      (node (ref "IC2") (pin "43") (pinfunction "GND_43") (pintype "power_in"))
      (node (ref "IC2") (pin "49") (pinfunction "PAD(GND)_49") (pintype "power_in"))
      (node (ref "IC2") (pin "6") (pinfunction "GND_6") (pintype "power_in"))
      (node (ref "IC2") (pin "7") (pinfunction "GND_7") (pintype "power_in"))
      (node (ref "IC4") (pin "18") (pinfunction "GND_18") (pintype "power_in"))
      (node (ref "IC4") (pin "23") (pinfunction "GND_23") (pintype "power_in"))
      (node (ref "IC4") (pin "27") (pinfunction "GND_27") (pintype "power_in"))
      (node (ref "IC4") (pin "31") (pinfunction "GND_31") (pintype "power_in"))
      (node (ref "IC4") (pin "34") (pinfunction "GND_34") (pintype "power_in"))
      (node (ref "IC4") (pin "38") (pinfunction "GND_38") (pintype "power_in"))
      (node (ref "IC4") (pin "43") (pinfunction "GND_43") (pintype "power_in"))
      (node (ref "IC4") (pin "49") (pinfunction "PAD(GND)_49") (pintype "power_in"))
      (node (ref "IC4") (pin "6") (pinfunction "GND_6") (pintype "power_in"))
      (node (ref "IC4") (pin "7") (pinfunction "GND_7") (pintype "power_in"))
      (node (ref "J10") (pin "SHIELD") (pinfunction "SHIELD_SHIELD") (pintype "passive"))
      (node (ref "J11") (pin "SHIELD") (pinfunction "SHIELD_SHIELD") (pintype "passive"))
      (node (ref "JP9") (pin "1") (pinfunction "E1_1") (pintype "passive"))
      (node (ref "R106") (pin "2") (pinfunction "2_2") (pintype "passive"))
      (node (ref "R107") (pin "2") (pinfunction "2_2") (pintype "passive"))
      (node (ref "R114") (pin "1") (pinfunction "1_1") (pintype "passive"))
      (node (ref "R127") (pin "1") (pinfunction "1_1") (pintype "passive"))
      (node (ref "R18") (pin "2") (pinfunction "2_2") (pintype "passive"))
      (node (ref "R19") (pin "2") (pinfunction "2_2") (pintype "passive"))
      (node (ref "R23") (pin "1") (pinfunction "1_1") (pintype "passive"))
      (node (ref "R25") (pin "1") (pinfunction "1_1") (pintype "passive"))
    )
    (net (code "43") (name "Net-(IC2-PDN)") (class "Default")
      (node (ref "IC2") (pin "30") (pinfunction "PDN_30") (pintype "input"))
      (node (ref "R29") (pin "2") (pinfunction "2_2") (pintype "passive"))
    )
    (net (code "44") (name "Net-(IC4-PDN)") (class "Default")
      (node (ref "IC4") (pin "30") (pinfunction "PDN_30") (pintype "input"))
      (node (ref "R36") (pin "2") (pinfunction "2_2") (pintype "passive"))
    )
    (net (code "45") (name "Net-(IC10-C1+)") (class "Default")
      (node (ref "C70") (pin "2") (pinfunction "2_2") (pintype "passive"))
      (node (ref "IC10") (pin "1") (pinfunction "C1+_1") (pintype "passive"))
    )
    (net (code "46") (name "Net-(IC10-C1-)") (class "Default")
      (node (ref "C70") (pin "1") (pinfunction "1_1") (pintype "passive"))
      (node (ref "IC10") (pin "3") (pinfunction "C1-_3") (pintype "passive"))
    )
    (net (code "47") (name "Net-(IC10-C2+)") (class "Default")
      (node (ref "C71") (pin "2") (pinfunction "2_2") (pintype "passive"))
      (node (ref "IC10") (pin "4") (pinfunction "C2+_4") (pintype "passive"))
    )
    (net (code "48") (name "Net-(IC10-C2-)") (class "Default")
      (node (ref "C71") (pin "1") (pinfunction "1_1") (pintype "passive"))
      (node (ref "IC10") (pin "5") (pinfunction "C2-_5") (pintype "passive"))
    )
    (net (code "49") (name "Net-(IC10-R1IN)") (class "Default")
      (node (ref "IC10") (pin "13") (pinfunction "R1IN_13") (pintype "input"))
      (node (ref "R117") (pin "2") (pinfunction "2_2") (pintype "passive"))
    )
    (net (code "50") (name "Net-(IC10-R2IN)") (class "Default")
      (node (ref "IC10") (pin "8") (pinfunction "R2IN_8") (pintype "input"))
      (node (ref "R118") (pin "2") (pinfunction "2_2") (pintype "passive"))
    )
    (net (code "51") (name "Net-(IC10-T1OUT)") (class "Default")
      (node (ref "IC10") (pin "14") (pinfunction "T1OUT_14") (pintype "output"))
      (node (ref "R113") (pin "2") (pinfunction "2_2") (pintype "passive"))
    )
    (net (code "52") (name "Net-(IC10-T2OUT)") (class "Default")
      (node (ref "IC10") (pin "7") (pinfunction "T2OUT_7") (pintype "output"))
      (node (ref "R116") (pin "2") (pinfunction "2_2") (pintype "passive"))
    )
    (net (code "53") (name "Net-(IC10-V+)") (class "Default")
      (node (ref "C72") (pin "1") (pinfunction "1_1") (pintype "passive"))
      (node (ref "IC10") (pin "2") (pinfunction "V+_2") (pintype "power_in"))
    )
    (net (code "54") (name "Net-(IC10-V-)") (class "Default")
      (node (ref "C88") (pin "1") (pinfunction "1_1") (pintype "passive"))
      (node (ref "IC10") (pin "6") (pinfunction "V-_6") (pintype "power_in"))
    )
    (net (code "55") (name "Net-(IC12-C1+)") (class "Default")
      (node (ref "C90") (pin "2") (pinfunction "2_2") (pintype "passive"))
      (node (ref "IC12") (pin "1") (pinfunction "C1+_1") (pintype "passive"))
    )
    (net (code "56") (name "Net-(IC12-C1-)") (class "Default")
      (node (ref "C90") (pin "1") (pinfunction "1_1") (pintype "passive"))
      (node (ref "IC12") (pin "3") (pinfunction "C1-_3") (pintype "passive"))
    )
    (net (code "57") (name "Net-(IC12-C2+)") (class "Default")
      (node (ref "C91") (pin "2") (pinfunction "2_2") (pintype "passive"))
      (node (ref "IC12") (pin "4") (pinfunction "C2+_4") (pintype "passive"))
    )
    (net (code "58") (name "Net-(IC12-C2-)") (class "Default")
      (node (ref "C91") (pin "1") (pinfunction "1_1") (pintype "passive"))
      (node (ref "IC12") (pin "5") (pinfunction "C2-_5") (pintype "passive"))
    )
    (net (code "59") (name "Net-(IC12-R1IN)") (class "Default")
      (node (ref "IC12") (pin "13") (pinfunction "R1IN_13") (pintype "input"))
      (node (ref "R121") (pin "2") (pinfunction "2_2") (pintype "passive"))
    )
    (net (code "60") (name "Net-(IC12-R2IN)") (class "Default")
      (node (ref "IC12") (pin "8") (pinfunction "R2IN_8") (pintype "input"))
      (node (ref "R125") (pin "2") (pinfunction "2_2") (pintype "passive"))
    )
    (net (code "61") (name "Net-(IC12-T1OUT)") (class "Default")
      (node (ref "IC12") (pin "14") (pinfunction "T1OUT_14") (pintype "output"))
      (node (ref "R119") (pin "2") (pinfunction "2_2") (pintype "passive"))
    )
    (net (code "62") (name "Net-(IC12-T2OUT)") (class "Default")
      (node (ref "IC12") (pin "7") (pinfunction "T2OUT_7") (pintype "output"))
      (node (ref "R120") (pin "2") (pinfunction "2_2") (pintype "passive"))
    )
    (net (code "63") (name "Net-(IC12-V+)") (class "Default")
      (node (ref "C92") (pin "1") (pinfunction "1_1") (pintype "passive"))
      (node (ref "IC12") (pin "2") (pinfunction "V+_2") (pintype "power_in"))
    )
    (net (code "64") (name "Net-(IC12-V-)") (class "Default")
      (node (ref "C93") (pin "1") (pinfunction "1_1") (pintype "passive"))
      (node (ref "IC12") (pin "6") (pinfunction "V-_6") (pintype "power_in"))
    )
    (net (code "65") (name "Net-(J10-Pad1)") (class "Default")
      (node (ref "J10") (pin "1") (pinfunction "1_1") (pintype "bidirectional"))
      (node (ref "R16") (pin "1") (pinfunction "1_1") (pintype "passive"))
      (node (ref "R8") (pin "1") (pinfunction "1_1") (pintype "passive"))
    )
    (net (code "66") (name "Net-(J10-Pad2)") (class "Default")
      (node (ref "J10") (pin "2") (pinfunction "2_2") (pintype "bidirectional"))
      (node (ref "R9") (pin "1") (pinfunction "1_1") (pintype "passive"))
    )
    (net (code "67") (name "Net-(J10-Pad3)") (class "Default")
      (node (ref "J10") (pin "3") (pinfunction "3_3") (pintype "bidirectional"))
      (node (ref "R10") (pin "1") (pinfunction "1_1") (pintype "passive"))
      (node (ref "R17") (pin "1") (pinfunction "1_1") (pintype "passive"))
    )
    (net (code "68") (name "Net-(J10-Pad4)") (class "Default")
      (node (ref "J10") (pin "4") (pinfunction "4_4") (pintype "bidirectional"))
      (node (ref "R11") (pin "1") (pinfunction "1_1") (pintype "passive"))
      (node (ref "R18") (pin "1") (pinfunction "1_1") (pintype "passive"))
    )
    (net (code "69") (name "Net-(J10-Pad5)") (class "Default")
      (node (ref "J10") (pin "5") (pinfunction "5_5") (pintype "bidirectional"))
      (node (ref "R12") (pin "1") (pinfunction "1_1") (pintype "passive"))
      (node (ref "R19") (pin "1") (pinfunction "1_1") (pintype "passive"))
    )
    (net (code "70") (name "Net-(J10-Pad6)") (class "Default")
      (node (ref "J10") (pin "6") (pinfunction "6_6") (pintype "bidirectional"))
      (node (ref "R13") (pin "1") (pinfunction "1_1") (pintype "passive"))
      (node (ref "R20") (pin "1") (pinfunction "1_1") (pintype "passive"))
    )
    (net (code "71") (name "Net-(J10-Pad7)") (class "Default")
      (node (ref "J10") (pin "7") (pinfunction "7_7") (pintype "bidirectional"))
      (node (ref "R14") (pin "1") (pinfunction "1_1") (pintype "passive"))
    )
    (net (code "72") (name "Net-(J10-Pad8)") (class "Default")
      (node (ref "J10") (pin "8") (pinfunction "8_8") (pintype "bidirectional"))
      (node (ref "R15") (pin "1") (pinfunction "1_1") (pintype "passive"))
      (node (ref "R21") (pin "1") (pinfunction "1_1") (pintype "passive"))
    )
    (net (code "73") (name "Net-(J11-Pad1)") (class "Default")
      (node (ref "J11") (pin "1") (pinfunction "1_1") (pintype "bidirectional"))
      (node (ref "R103") (pin "1") (pinfunction "1_1") (pintype "passive"))
      (node (ref "R28") (pin "1") (pinfunction "1_1") (pintype "passive"))
    )
    (net (code "74") (name "Net-(J11-Pad2)") (class "Default")
      (node (ref "J11") (pin "2") (pinfunction "2_2") (pintype "bidirectional"))
      (node (ref "R30") (pin "1") (pinfunction "1_1") (pintype "passive"))
    )
    (net (code "75") (name "Net-(J11-Pad3)") (class "Default")
      (node (ref "J11") (pin "3") (pinfunction "3_3") (pintype "bidirectional"))
      (node (ref "R104") (pin "1") (pinfunction "1_1") (pintype "passive"))
      (node (ref "R32") (pin "1") (pinfunction "1_1") (pintype "passive"))
    )
    (net (code "76") (name "Net-(J11-Pad4)") (class "Default")
      (node (ref "J11") (pin "4") (pinfunction "4_4") (pintype "bidirectional"))
      (node (ref "R106") (pin "1") (pinfunction "1_1") (pintype "passive"))
      (node (ref "R33") (pin "1") (pinfunction "1_1") (pintype "passive"))
    )
    (net (code "77") (name "Net-(J11-Pad5)") (class "Default")
      (node (ref "J11") (pin "5") (pinfunction "5_5") (pintype "bidirectional"))
      (node (ref "R107") (pin "1") (pinfunction "1_1") (pintype "passive"))
      (node (ref "R34") (pin "1") (pinfunction "1_1") (pintype "passive"))
    )
    (net (code "78") (name "Net-(J11-Pad6)") (class "Default")
      (node (ref "J11") (pin "6") (pinfunction "6_6") (pintype "bidirectional"))
      (node (ref "R100") (pin "1") (pinfunction "1_1") (pintype "passive"))
      (node (ref "R108") (pin "1") (pinfunction "1_1") (pintype "passive"))
    )
    (net (code "79") (name "Net-(J11-Pad7)") (class "Default")
      (node (ref "J11") (pin "7") (pinfunction "7_7") (pintype "bidirectional"))
      (node (ref "R101") (pin "1") (pinfunction "1_1") (pintype "passive"))
    )
    (net (code "80") (name "Net-(J11-Pad8)") (class "Default")
      (node (ref "J11") (pin "8") (pinfunction "8_8") (pintype "bidirectional"))
      (node (ref "R102") (pin "1") (pinfunction "1_1") (pintype "passive"))
      (node (ref "R110") (pin "1") (pinfunction "1_1") (pintype "passive"))
    )
    (net (code "81") (name "P3V3") (class "Default")
      (node (ref "C102") (pin "1") (pinfunction "1_1") (pintype "passive"))
      (node (ref "C67") (pin "2") (pinfunction "2_2") (pintype "passive"))
      (node (ref "C80") (pin "1") (pinfunction "1_1") (pintype "passive"))
      (node (ref "C81") (pin "1") (pinfunction "1_1") (pintype "passive"))
      (node (ref "C84") (pin "1") (pinfunction "1_1") (pintype "passive"))
      (node (ref "C85") (pin "1") (pinfunction "1_1") (pintype "passive"))
      (node (ref "C86") (pin "1") (pinfunction "1_1") (pintype "passive"))
      (node (ref "C87") (pin "1") (pinfunction "1_1") (pintype "passive"))
      (node (ref "C89") (pin "2") (pinfunction "2_2") (pintype "passive"))
      (node (ref "C94") (pin "1") (pinfunction "1_1") (pintype "passive"))
      (node (ref "C95") (pin "1") (pinfunction "1_1") (pintype "passive"))
      (node (ref "C96") (pin "1") (pinfunction "1_1") (pintype "passive"))
      (node (ref "C97") (pin "1") (pinfunction "1_1") (pintype "passive"))
      (node (ref "C98") (pin "1") (pinfunction "1_1") (pintype "passive"))
      (node (ref "D3") (pin "5") (pinfunction "VBUS_5") (pintype "power_in"))
      (node (ref "D4") (pin "5") (pinfunction "VBUS_5") (pintype "power_in"))
      (node (ref "D5") (pin "5") (pinfunction "VBUS_5") (pintype "power_in"))
      (node (ref "D6") (pin "5") (pinfunction "VBUS_5") (pintype "power_in"))
      (node (ref "IC10") (pin "16") (pinfunction "VCC_16") (pintype "power_in"))
      (node (ref "IC12") (pin "16") (pinfunction "VCC_16") (pintype "power_in"))
      (node (ref "IC2") (pin "11") (pinfunction "Vcc_11") (pintype "power_in"))
      (node (ref "IC2") (pin "15") (pinfunction "Vcc_15") (pintype "power_in"))
      (node (ref "IC2") (pin "16") (pinfunction "Vcc_16") (pintype "power_in"))
      (node (ref "IC2") (pin "2") (pinfunction "Vcc_2") (pintype "power_in"))
      (node (ref "IC2") (pin "24") (pinfunction "Vcc_24") (pintype "power_in"))
      (node (ref "IC2") (pin "37") (pinfunction "Vcc_37") (pintype "power_in"))
      (node (ref "IC2") (pin "45") (pinfunction "Vcc_45") (pintype "power_in"))
      (node (ref "IC2") (pin "46") (pinfunction "Vcc_46") (pintype "power_in"))
      (node (ref "IC4") (pin "11") (pinfunction "Vcc_11") (pintype "power_in"))
      (node (ref "IC4") (pin "15") (pinfunction "Vcc_15") (pintype "power_in"))
      (node (ref "IC4") (pin "16") (pinfunction "Vcc_16") (pintype "power_in"))
      (node (ref "IC4") (pin "2") (pinfunction "Vcc_2") (pintype "power_in"))
      (node (ref "IC4") (pin "24") (pinfunction "Vcc_24") (pintype "power_in"))
      (node (ref "IC4") (pin "37") (pinfunction "Vcc_37") (pintype "power_in"))
      (node (ref "IC4") (pin "45") (pinfunction "Vcc_45") (pintype "power_in"))
      (node (ref "IC4") (pin "46") (pinfunction "Vcc_46") (pintype "power_in"))
      (node (ref "R133") (pin "1") (pinfunction "1_1") (pintype "passive"))
      (node (ref "R135") (pin "1") (pinfunction "1_1") (pintype "passive"))
      (node (ref "R29") (pin "1") (pinfunction "1_1") (pintype "passive"))
      (node (ref "R35") (pin "1") (pinfunction "1_1") (pintype "passive"))
      (node (ref "R36") (pin "1") (pinfunction "1_1") (pintype "passive"))
      (node (ref "R44") (pin "1") (pinfunction "1_1") (pintype "passive"))
    )
    (net (code "82") (name "unconnected-(IC2-nc-Pad17)") (class "Default")
      (node (ref "IC2") (pin "17") (pinfunction "nc_17") (pintype "passive"))
    )
    (net (code "83") (name "unconnected-(IC2-nc-Pad44)") (class "Default")
      (node (ref "IC2") (pin "44") (pinfunction "nc_44") (pintype "power_in"))
    )
    (net (code "84") (name "unconnected-(IC4-nc-Pad17)") (class "Default")
      (node (ref "IC4") (pin "17") (pinfunction "nc_17") (pintype "passive"))
    )
    (net (code "85") (name "unconnected-(IC4-nc-Pad44)") (class "Default")
      (node (ref "IC4") (pin "44") (pinfunction "nc_44") (pintype "power_in"))
    )
  )
)
